# IRController.net
KiCad netlist of a schematic drawn in EAGLE
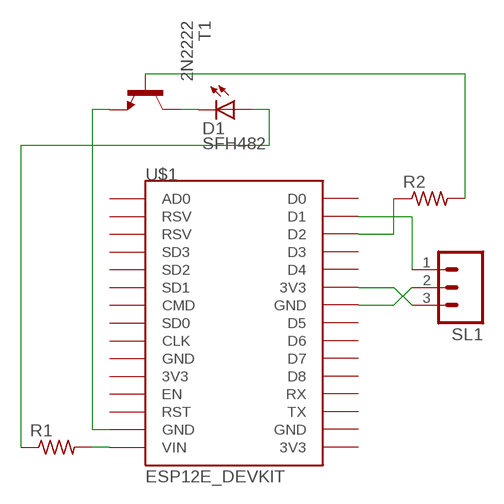
[diagram p0: schematic, sheet 1]

(export (version "E")
  (design (tool "Eeschema 10.0.6"))
  (components
    (comp (ref "D1")
      (value "SFH482")
      (footprint "eagle-import:SFH482")
      (libsource (lib "eagle-import") (part "SFH482"))
    )
    (comp (ref "R1")
      (value "R-US_0204/2V")
      (footprint "eagle-import:0204V")
      (libsource (lib "eagle-import") (part "R-US_0204/2V"))
    )
    (comp (ref "R2")
      (value "R-US_0204/2V")
      (footprint "eagle-import:0204V")
      (libsource (lib "eagle-import") (part "R-US_0204/2V"))
    )
    (comp (ref "SL1")
      (value "MA03")
      (footprint "eagle-import:03P")
      (libsource (lib "eagle-import") (part "MA03"))
    )
    (comp (ref "T1")
      (value "2N2222")
      (footprint "eagle-import:TO18")
      (libsource (lib "eagle-import") (part "2N2222"))
    )
    (comp (ref "U$1")
      (value "ESP12E_DEVKIT")
      (footprint "eagle-import:ESP12E_DEVKIT")
      (libsource (lib "eagle-import") (part "ESP12E_DEVKIT"))
    )
  )
  (nets
    (net (code "1") (name "Net-(D1-C)") (class "Default")
      (node (ref "D1") (pin "K") (pinfunction "C_K") (pintype "passive"))
      (node (ref "T1") (pin "3") (pinfunction "C_3") (pintype "passive"))
    )
    (net (code "2") (name "Net-(D1-PadA)") (class "Default")
      (node (ref "D1") (pin "A") (pinfunction "A_A") (pintype "passive"))
      (node (ref "R1") (pin "1") (pinfunction "1_1") (pintype "passive"))
    )
    (net (code "3") (name "Net-(R1-Pad2)") (class "Default")
      (node (ref "R1") (pin "2") (pinfunction "2_2") (pintype "passive"))
      (node (ref "U$1") (pin "VIN") (pinfunction "VIN_VIN") (pintype "bidirectional"))
    )
    (net (code "4") (name "Net-(R2-Pad1)") (class "Default")
      (node (ref "R2") (pin "1") (pinfunction "1_1") (pintype "passive"))
      (node (ref "U$1") (pin "D2") (pinfunction "D2_D2") (pintype "bidirectional"))
    )
    (net (code "5") (name "Net-(SL1-Pad1)") (class "Default")
      (node (ref "SL1") (pin "1") (pinfunction "1_1") (pintype "passive"))
      (node (ref "U$1") (pin "D1") (pinfunction "D1_D1") (pintype "bidirectional"))
    )
    (net (code "6") (name "Net-(SL1-Pad2)") (class "Default")
      (node (ref "SL1") (pin "2") (pinfunction "2_2") (pintype "passive"))
      (node (ref "U$1") (pin "GND@2") (pinfunction "GND_GND@2") (pintype "bidirectional"))
    )
    (net (code "7") (name "Net-(SL1-Pad3)") (class "Default")
      (node (ref "SL1") (pin "3") (pinfunction "3_3") (pintype "passive"))
      (node (ref "U$1") (pin "3V3@1") (pinfunction "3V3_3V3@1") (pintype "bidirectional"))
    )
    (net (code "8") (name "Net-(T1-B)") (class "Default")
      (node (ref "R2") (pin "2") (pinfunction "2_2") (pintype "passive"))
      (node (ref "T1") (pin "2") (pinfunction "B_2") (pintype "passive"))
    )
    (net (code "9") (name "Net-(T1-E)") (class "Default")
      (node (ref "T1") (pin "1") (pinfunction "E_1") (pintype "passive"))
      (node (ref "U$1") (pin "GND@1") (pinfunction "GND_GND@1") (pintype "bidirectional"))
    )
    (net (code "10") (name "unconnected-(U$1-3V3-Pad3V3@0)") (class "Default")
      (node (ref "U$1") (pin "3V3@0") (pinfunction "3V3_3V3@0") (pintype "bidirectional"))
    )
    (net (code "11") (name "unconnected-(U$1-3V3-Pad3V3@2)") (class "Default")
      (node (ref "U$1") (pin "3V3@2") (pinfunction "3V3_3V3@2") (pintype "bidirectional"))
    )
    (net (code "12") (name "unconnected-(U$1-GND-PadGND@0)") (class "Default")
      (node (ref "U$1") (pin "GND@0") (pinfunction "GND_GND@0") (pintype "bidirectional"))
    )
    (net (code "13") (name "unconnected-(U$1-GND-PadGND@3)") (class "Default")
      (node (ref "U$1") (pin "GND@3") (pinfunction "GND_GND@3") (pintype "bidirectional"))
    )
    (net (code "14") (name "unconnected-(U$1-PadAD0)") (class "Default")
      (node (ref "U$1") (pin "AD0") (pinfunction "AD0_AD0") (pintype "bidirectional"))
    )
    (net (code "15") (name "unconnected-(U$1-PadCLK)") (class "Default")
      (node (ref "U$1") (pin "CLK") (pinfunction "CLK_CLK") (pintype "bidirectional"))
    )
    (net (code "16") (name "unconnected-(U$1-PadCMD)") (class "Default")
      (node (ref "U$1") (pin "CMD") (pinfunction "CMD_CMD") (pintype "bidirectional"))
    )
    (net (code "17") (name "unconnected-(U$1-PadD0)") (class "Default")
      (node (ref "U$1") (pin "D0") (pinfunction "D0_D0") (pintype "bidirectional"))
    )
    (net (code "18") (name "unconnected-(U$1-PadD3)") (class "Default")
      (node (ref "U$1") (pin "D3") (pinfunction "D3_D3") (pintype "bidirectional"))
    )
    (net (code "19") (name "unconnected-(U$1-PadD4)") (class "Default")
      (node (ref "U$1") (pin "D4") (pinfunction "D4_D4") (pintype "bidirectional"))
    )
    (net (code "20") (name "unconnected-(U$1-PadD5)") (class "Default")
      (node (ref "U$1") (pin "D5") (pinfunction "D5_D5") (pintype "bidirectional"))
    )
    (net (code "21") (name "unconnected-(U$1-PadD6)") (class "Default")
      (node (ref "U$1") (pin "D6") (pinfunction "D6_D6") (pintype "bidirectional"))
    )
    (net (code "22") (name "unconnected-(U$1-PadD7)") (class "Default")
      (node (ref "U$1") (pin "D7") (pinfunction "D7_D7") (pintype "bidirectional"))
    )
    (net (code "23") (name "unconnected-(U$1-PadD8)") (class "Default")
      (node (ref "U$1") (pin "D8") (pinfunction "D8_D8") (pintype "bidirectional"))
    )
    (net (code "24") (name "unconnected-(U$1-PadEN)") (class "Default")
      (node (ref "U$1") (pin "EN") (pinfunction "EN_EN") (pintype "bidirectional"))
    )
    (net (code "25") (name "unconnected-(U$1-PadRST)") (class "Default")
      (node (ref "U$1") (pin "RST") (pinfunction "RST_RST") (pintype "bidirectional"))
    )
    (net (code "26") (name "unconnected-(U$1-PadRX)") (class "Default")
      (node (ref "U$1") (pin "RX") (pinfunction "RX_RX") (pintype "bidirectional"))
    )
    (net (code "27") (name "unconnected-(U$1-PadSD0)") (class "Default")
      (node (ref "U$1") (pin "SD0") (pinfunction "SD0_SD0") (pintype "bidirectional"))
    )
    (net (code "28") (name "unconnected-(U$1-PadSD1)") (class "Default")
      (node (ref "U$1") (pin "SD1") (pinfunction "SD1_SD1") (pintype "bidirectional"))
    )
    (net (code "29") (name "unconnected-(U$1-PadSD2)") (class "Default")
      (node (ref "U$1") (pin "SD2") (pinfunction "SD2_SD2") (pintype "bidirectional"))
    )
    (net (code "30") (name "unconnected-(U$1-PadSD3)") (class "Default")
      (node (ref "U$1") (pin "SD3") (pinfunction "SD3_SD3") (pintype "bidirectional"))
    )
    (net (code "31") (name "unconnected-(U$1-PadTX)") (class "Default")
      (node (ref "U$1") (pin "TX") (pinfunction "TX_TX") (pintype "bidirectional"))
    )
    (net (code "32") (name "unconnected-(U$1-RSV-PadRSV@0)") (class "Default")
      (node (ref "U$1") (pin "RSV@0") (pinfunction "RSV_RSV@0") (pintype "bidirectional"))
    )
    (net (code "33") (name "unconnected-(U$1-RSV-PadRSV@1)") (class "Default")
      (node (ref "U$1") (pin "RSV@1") (pinfunction "RSV_RSV@1") (pintype "bidirectional"))
    )
  )
)
